# sensore_linea.net
KiCad netlist of a schematic drawn in EAGLE
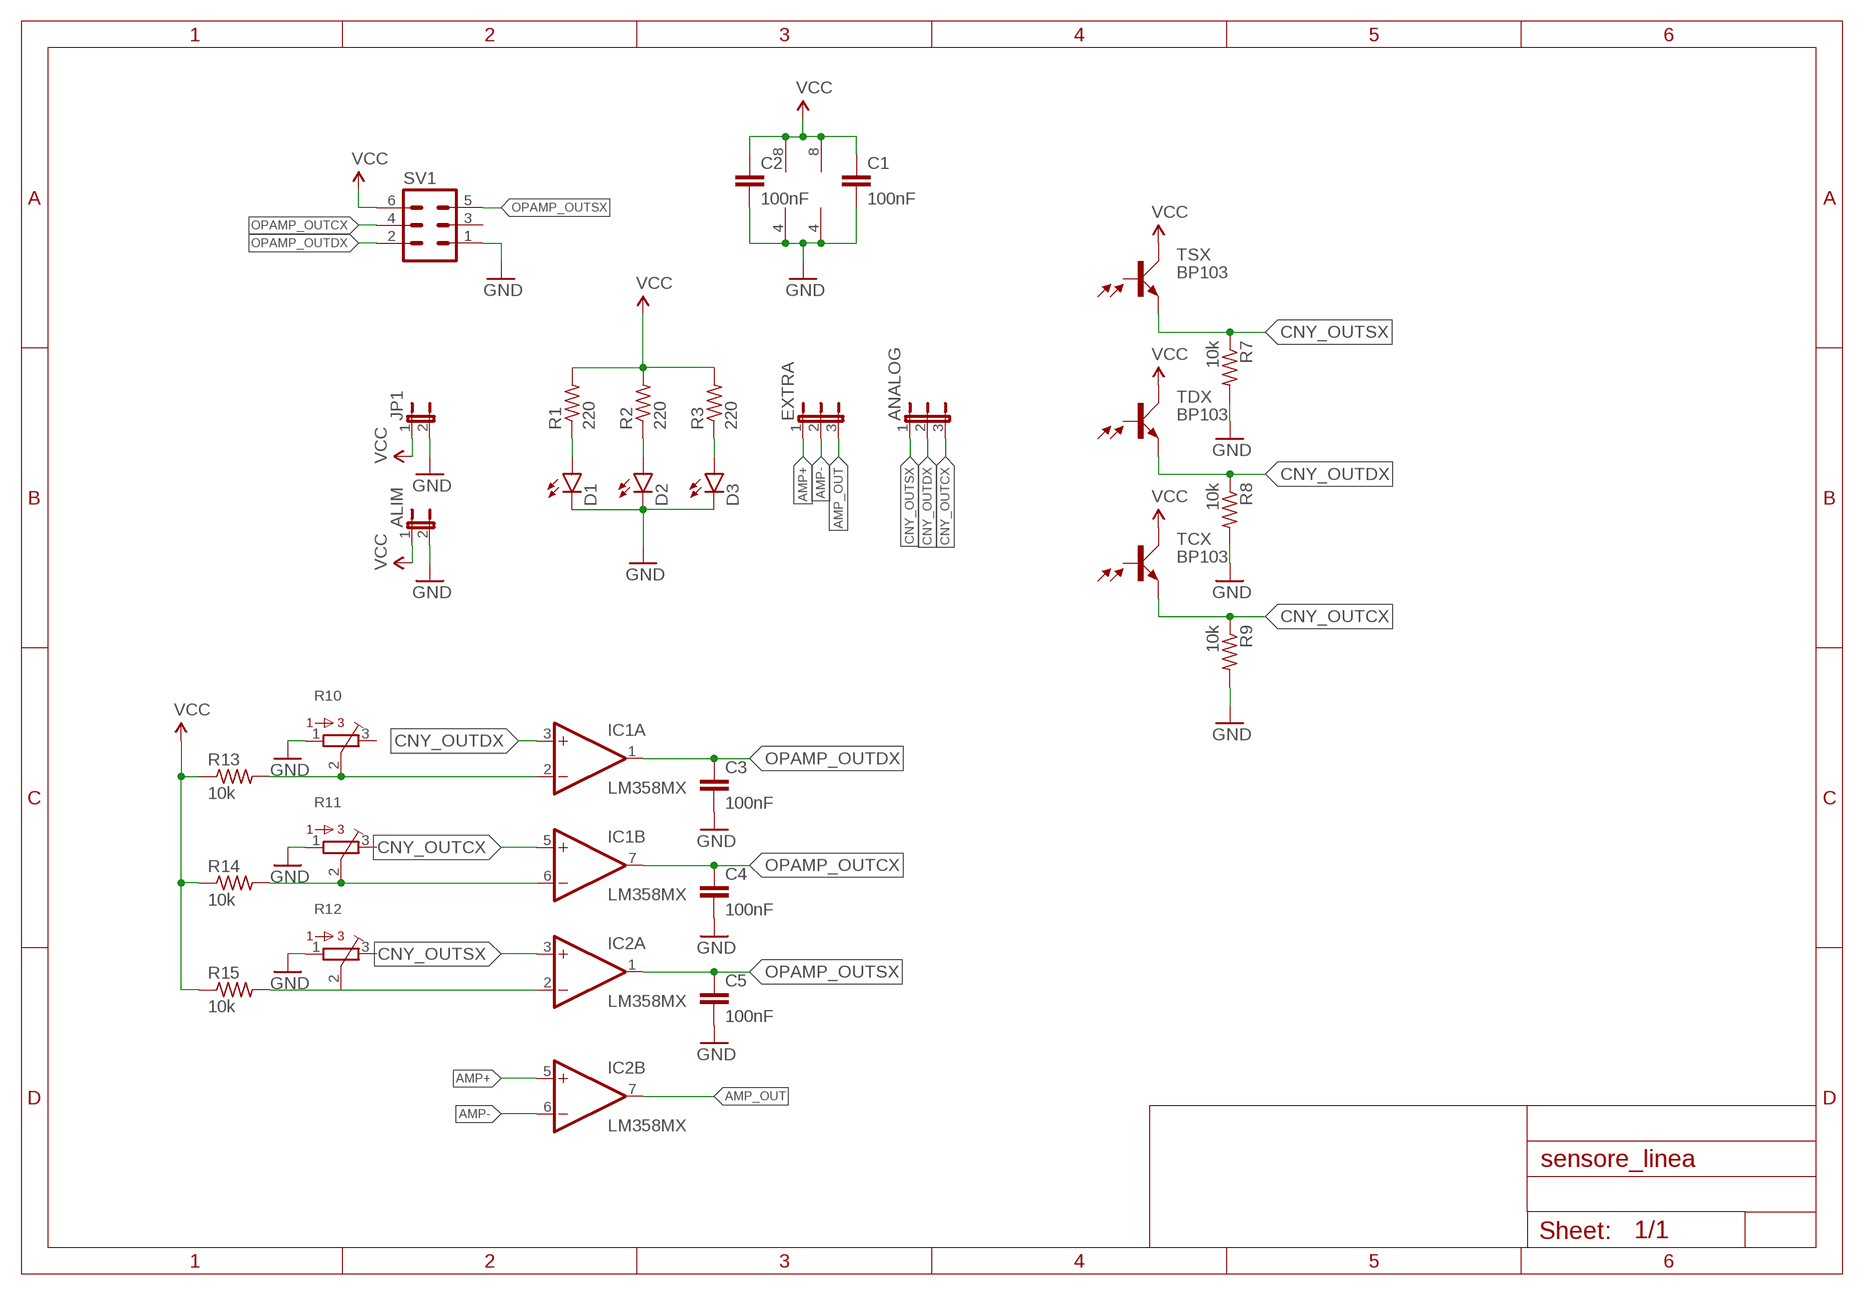
[diagram p0: schematic, sheet 1]

(export (version "E")
  (design (tool "Eeschema 10.0.6"))
  (components
    (comp (ref "ALIM")
      (value "JP1E")
      (footprint "eagle-import:JP1")
      (libsource (lib "eagle-import") (part "JP1E"))
    )
    (comp (ref "ANALOG")
      (value "JP2E")
      (footprint "eagle-import:JP2")
      (libsource (lib "eagle-import") (part "JP2E"))
    )
    (comp (ref "C1")
      (value "100nF")
      (footprint "eagle-import:C2.5-2")
      (libsource (lib "eagle-import") (part "C2.5/2"))
    )
    (comp (ref "C2")
      (value "100nF")
      (footprint "eagle-import:C2.5-2")
      (libsource (lib "eagle-import") (part "C2.5/2"))
    )
    (comp (ref "C3")
      (value "100nF")
      (footprint "eagle-import:C2.5-2")
      (libsource (lib "eagle-import") (part "C2.5/2"))
    )
    (comp (ref "C4")
      (value "100nF")
      (footprint "eagle-import:C2.5-2")
      (libsource (lib "eagle-import") (part "C2.5/2"))
    )
    (comp (ref "C5")
      (value "100nF")
      (footprint "eagle-import:C2.5-2")
      (libsource (lib "eagle-import") (part "C2.5/2"))
    )
    (comp (ref "D1")
      (value "LED3MM")
      (footprint "eagle-import:LED3MM")
      (libsource (lib "eagle-import") (part "LED3MM"))
    )
    (comp (ref "D2")
      (value "LED3MM")
      (footprint "eagle-import:LED3MM")
      (libsource (lib "eagle-import") (part "LED3MM"))
    )
    (comp (ref "D3")
      (value "LED3MM")
      (footprint "eagle-import:LED3MM")
      (libsource (lib "eagle-import") (part "LED3MM"))
    )
    (comp (ref "EXTRA")
      (value "JP2E")
      (footprint "eagle-import:JP2")
      (libsource (lib "eagle-import") (part "JP2E"))
    )
    (comp (ref "IC1")
      (value "LM358MX")
      (footprint "eagle-import:SO08")
      (libsource (lib "eagle-import") (part "LM358MX"))
    )
    (comp (ref "IC2")
      (value "LM358MX")
      (footprint "eagle-import:SO08")
      (libsource (lib "eagle-import") (part "LM358MX"))
    )
    (comp (ref "JP1")
      (value "JP1E")
      (footprint "eagle-import:JP1")
      (libsource (lib "eagle-import") (part "JP1E"))
    )
    (comp (ref "R1")
      (value "220")
      (footprint "eagle-import:0207_7")
      (libsource (lib "eagle-import") (part "R-US_0207/7"))
    )
    (comp (ref "R2")
      (value "220")
      (footprint "eagle-import:0207_7")
      (libsource (lib "eagle-import") (part "R-US_0207/7"))
    )
    (comp (ref "R3")
      (value "220")
      (footprint "eagle-import:0207_7")
      (libsource (lib "eagle-import") (part "R-US_0207/7"))
    )
    (comp (ref "R7")
      (value "10k")
      (footprint "eagle-import:0207_7")
      (libsource (lib "eagle-import") (part "R-US_0207/7"))
    )
    (comp (ref "R8")
      (value "10k")
      (footprint "eagle-import:0207_7")
      (libsource (lib "eagle-import") (part "R-US_0207/7"))
    )
    (comp (ref "R9")
      (value "10k")
      (footprint "eagle-import:0207_7")
      (libsource (lib "eagle-import") (part "R-US_0207/7"))
    )
    (comp (ref "R10")
      (value "3386-J")
      (footprint "eagle-import:3386J")
      (libsource (lib "eagle-import") (part "3386-J"))
    )
    (comp (ref "R11")
      (value "3386-J")
      (footprint "eagle-import:3386J")
      (libsource (lib "eagle-import") (part "3386-J"))
    )
    (comp (ref "R12")
      (value "3386-J")
      (footprint "eagle-import:3386J")
      (libsource (lib "eagle-import") (part "3386-J"))
    )
    (comp (ref "R13")
      (value "10k")
      (footprint "eagle-import:0207_7")
      (libsource (lib "eagle-import") (part "R-US_0207/7"))
    )
    (comp (ref "R14")
      (value "10k")
      (footprint "eagle-import:0207_7")
      (libsource (lib "eagle-import") (part "R-US_0207/7"))
    )
    (comp (ref "R15")
      (value "10k")
      (footprint "eagle-import:0207_7")
      (libsource (lib "eagle-import") (part "R-US_0207/7"))
    )
    (comp (ref "SV1")
      (value "MA03-2")
      (footprint "eagle-import:MA03-2")
      (libsource (lib "eagle-import") (part "MA03-2"))
    )
    (comp (ref "TCX")
      (value "BP103")
      (footprint "eagle-import:BP103")
      (libsource (lib "eagle-import") (part "BP103"))
    )
    (comp (ref "TDX")
      (value "BP103")
      (footprint "eagle-import:BP103")
      (libsource (lib "eagle-import") (part "BP103"))
    )
    (comp (ref "TSX")
      (value "BP103")
      (footprint "eagle-import:BP103")
      (libsource (lib "eagle-import") (part "BP103"))
    )
  )
  (nets
    (net (code "1") (name "AMP+") (class "Default")
      (node (ref "EXTRA") (pin "1") (pinfunction "1_1") (pintype "passive"))
      (node (ref "IC2") (pin "5") (pinfunction "+IN_5") (pintype "input"))
    )
    (net (code "2") (name "AMP-") (class "Default")
      (node (ref "EXTRA") (pin "2") (pinfunction "2_2") (pintype "passive"))
      (node (ref "IC2") (pin "6") (pinfunction "-IN_6") (pintype "input"))
    )
    (net (code "3") (name "AMP_OUT") (class "Default")
      (node (ref "EXTRA") (pin "3") (pinfunction "3_3") (pintype "passive"))
      (node (ref "IC2") (pin "7") (pinfunction "OUT_7") (pintype "output"))
    )
    (net (code "4") (name "CNY_OUTCX") (class "Default")
      (node (ref "ANALOG") (pin "3") (pinfunction "3_3") (pintype "passive"))
      (node (ref "IC1") (pin "5") (pinfunction "+IN_5") (pintype "input"))
      (node (ref "R9") (pin "1") (pinfunction "1_1") (pintype "passive"))
      (node (ref "TCX") (pin "E") (pinfunction "E_E") (pintype "passive"))
    )
    (net (code "5") (name "CNY_OUTDX") (class "Default")
      (node (ref "ANALOG") (pin "2") (pinfunction "2_2") (pintype "passive"))
      (node (ref "IC1") (pin "3") (pinfunction "+IN_3") (pintype "input"))
      (node (ref "R8") (pin "1") (pinfunction "1_1") (pintype "passive"))
      (node (ref "TDX") (pin "E") (pinfunction "E_E") (pintype "passive"))
    )
    (net (code "6") (name "CNY_OUTSX") (class "Default")
      (node (ref "ANALOG") (pin "1") (pinfunction "1_1") (pintype "passive"))
      (node (ref "IC2") (pin "3") (pinfunction "+IN_3") (pintype "input"))
      (node (ref "R7") (pin "1") (pinfunction "1_1") (pintype "passive"))
      (node (ref "TSX") (pin "E") (pinfunction "E_E") (pintype "passive"))
    )
    (net (code "7") (name "GND") (class "Default")
      (node (ref "ALIM") (pin "2") (pinfunction "2_2") (pintype "passive"))
      (node (ref "C1") (pin "2") (pinfunction "2_2") (pintype "passive"))
      (node (ref "C2") (pin "2") (pinfunction "2_2") (pintype "passive"))
      (node (ref "C3") (pin "2") (pinfunction "2_2") (pintype "passive"))
      (node (ref "C4") (pin "2") (pinfunction "2_2") (pintype "passive"))
      (node (ref "C5") (pin "2") (pinfunction "2_2") (pintype "passive"))
      (node (ref "D1") (pin "K") (pinfunction "C_K") (pintype "passive"))
      (node (ref "D2") (pin "K") (pinfunction "C_K") (pintype "passive"))
      (node (ref "D3") (pin "K") (pinfunction "C_K") (pintype "passive"))
      (node (ref "IC1") (pin "4") (pinfunction "V-_4") (pintype "power_in"))
      (node (ref "IC2") (pin "4") (pinfunction "V-_4") (pintype "power_in"))
      (node (ref "JP1") (pin "2") (pinfunction "2_2") (pintype "passive"))
      (node (ref "R10") (pin "1") (pinfunction "1_1") (pintype "passive"))
      (node (ref "R11") (pin "1") (pinfunction "1_1") (pintype "passive"))
      (node (ref "R12") (pin "1") (pinfunction "1_1") (pintype "passive"))
      (node (ref "R7") (pin "2") (pinfunction "2_2") (pintype "passive"))
      (node (ref "R8") (pin "2") (pinfunction "2_2") (pintype "passive"))
      (node (ref "R9") (pin "2") (pinfunction "2_2") (pintype "passive"))
      (node (ref "SV1") (pin "1") (pinfunction "1_1") (pintype "passive"))
    )
    (net (code "8") (name "Net-(D1-PadA)") (class "Default")
      (node (ref "D1") (pin "A") (pinfunction "A_A") (pintype "passive"))
      (node (ref "R1") (pin "1") (pinfunction "1_1") (pintype "passive"))
    )
    (net (code "9") (name "Net-(D2-PadA)") (class "Default")
      (node (ref "D2") (pin "A") (pinfunction "A_A") (pintype "passive"))
      (node (ref "R2") (pin "1") (pinfunction "1_1") (pintype "passive"))
    )
    (net (code "10") (name "Net-(D3-PadA)") (class "Default")
      (node (ref "D3") (pin "A") (pinfunction "A_A") (pintype "passive"))
      (node (ref "R3") (pin "1") (pinfunction "1_1") (pintype "passive"))
    )
    (net (code "11") (name "Net-(IC1A--IN)") (class "Default")
      (node (ref "IC1") (pin "2") (pinfunction "-IN_2") (pintype "input"))
      (node (ref "R10") (pin "2") (pinfunction "2_2") (pintype "passive"))
      (node (ref "R13") (pin "2") (pinfunction "2_2") (pintype "passive"))
    )
    (net (code "12") (name "Net-(IC1B--IN)") (class "Default")
      (node (ref "IC1") (pin "6") (pinfunction "-IN_6") (pintype "input"))
      (node (ref "R11") (pin "2") (pinfunction "2_2") (pintype "passive"))
      (node (ref "R14") (pin "2") (pinfunction "2_2") (pintype "passive"))
    )
    (net (code "13") (name "Net-(IC2A--IN)") (class "Default")
      (node (ref "IC2") (pin "2") (pinfunction "-IN_2") (pintype "input"))
      (node (ref "R12") (pin "2") (pinfunction "2_2") (pintype "passive"))
      (node (ref "R15") (pin "2") (pinfunction "2_2") (pintype "passive"))
    )
    (net (code "14") (name "OPAMP_OUTCX") (class "Default")
      (node (ref "C4") (pin "1") (pinfunction "1_1") (pintype "passive"))
      (node (ref "IC1") (pin "7") (pinfunction "OUT_7") (pintype "output"))
      (node (ref "SV1") (pin "4") (pinfunction "4_4") (pintype "passive"))
    )
    (net (code "15") (name "OPAMP_OUTDX") (class "Default")
      (node (ref "C3") (pin "1") (pinfunction "1_1") (pintype "passive"))
      (node (ref "IC1") (pin "1") (pinfunction "OUT_1") (pintype "output"))
      (node (ref "SV1") (pin "2") (pinfunction "2_2") (pintype "passive"))
    )
    (net (code "16") (name "OPAMP_OUTSX") (class "Default")
      (node (ref "C5") (pin "1") (pinfunction "1_1") (pintype "passive"))
      (node (ref "IC2") (pin "1") (pinfunction "OUT_1") (pintype "output"))
      (node (ref "SV1") (pin "5") (pinfunction "5_5") (pintype "passive"))
    )
    (net (code "17") (name "VCC") (class "Default")
      (node (ref "ALIM") (pin "1") (pinfunction "1_1") (pintype "passive"))
      (node (ref "C1") (pin "1") (pinfunction "1_1") (pintype "passive"))
      (node (ref "C2") (pin "1") (pinfunction "1_1") (pintype "passive"))
      (node (ref "IC1") (pin "8") (pinfunction "V+_8") (pintype "power_in"))
      (node (ref "IC2") (pin "8") (pinfunction "V+_8") (pintype "power_in"))
      (node (ref "JP1") (pin "1") (pinfunction "1_1") (pintype "passive"))
      (node (ref "R1") (pin "2") (pinfunction "2_2") (pintype "passive"))
      (node (ref "R13") (pin "1") (pinfunction "1_1") (pintype "passive"))
      (node (ref "R14") (pin "1") (pinfunction "1_1") (pintype "passive"))
      (node (ref "R15") (pin "1") (pinfunction "1_1") (pintype "passive"))
      (node (ref "R2") (pin "2") (pinfunction "2_2") (pintype "passive"))
      (node (ref "R3") (pin "2") (pinfunction "2_2") (pintype "passive"))
      (node (ref "SV1") (pin "6") (pinfunction "6_6") (pintype "passive"))
      (node (ref "TCX") (pin "C") (pinfunction "C_C") (pintype "passive"))
      (node (ref "TDX") (pin "C") (pinfunction "C_C") (pintype "passive"))
      (node (ref "TSX") (pin "C") (pinfunction "C_C") (pintype "passive"))
    )
    (net (code "18") (name "unconnected-(R10-Pad3)") (class "Default")
      (node (ref "R10") (pin "3") (pinfunction "3_3") (pintype "passive"))
    )
    (net (code "19") (name "unconnected-(R11-Pad3)") (class "Default")
      (node (ref "R11") (pin "3") (pinfunction "3_3") (pintype "passive"))
    )
    (net (code "20") (name "unconnected-(R12-Pad3)") (class "Default")
      (node (ref "R12") (pin "3") (pinfunction "3_3") (pintype "passive"))
    )
    (net (code "21") (name "unconnected-(SV1-Pad3)") (class "Default")
      (node (ref "SV1") (pin "3") (pinfunction "3_3") (pintype "passive"))
    )
    (net (code "22") (name "unconnected-(TCX-PadB)") (class "Default")
      (node (ref "TCX") (pin "B") (pinfunction "B_B") (pintype "passive"))
    )
    (net (code "23") (name "unconnected-(TDX-PadB)") (class "Default")
      (node (ref "TDX") (pin "B") (pinfunction "B_B") (pintype "passive"))
    )
    (net (code "24") (name "unconnected-(TSX-PadB)") (class "Default")
      (node (ref "TSX") (pin "B") (pinfunction "B_B") (pintype "passive"))
    )
  )
)
